# three_digit_CC_PNP.net
KiCad netlist of a schematic drawn in EAGLE
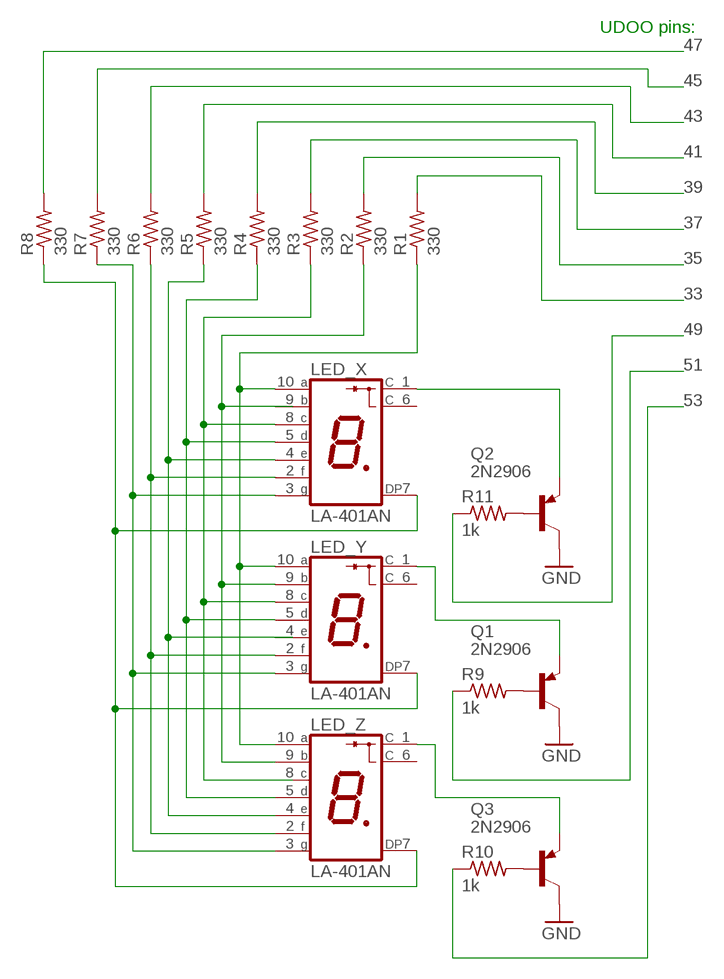
[diagram p0: schematic, sheet 1]

(export (version "E")
  (design (tool "Eeschema 10.0.6"))
  (components
    (comp (ref "LED_X")
      (value "LA-401AN")
      (footprint "eagle-import:LA-401")
      (libsource (lib "eagle-import") (part "LA-401NA"))
    )
    (comp (ref "LED_Y")
      (value "LA-401AN")
      (footprint "eagle-import:LA-401")
      (libsource (lib "eagle-import") (part "LA-401NA"))
    )
    (comp (ref "LED_Z")
      (value "LA-401AN")
      (footprint "eagle-import:LA-401")
      (libsource (lib "eagle-import") (part "LA-401NA"))
    )
    (comp (ref "Q1")
      (value "2N2906")
      (footprint "eagle-import:TO18")
      (libsource (lib "eagle-import") (part "2N2906"))
    )
    (comp (ref "Q2")
      (value "2N2906")
      (footprint "eagle-import:TO18")
      (libsource (lib "eagle-import") (part "2N2906"))
    )
    (comp (ref "Q3")
      (value "2N2906")
      (footprint "eagle-import:TO18")
      (libsource (lib "eagle-import") (part "2N2906"))
    )
    (comp (ref "R1")
      (value "330")
      (footprint "eagle-import:0204_7")
      (libsource (lib "eagle-import") (part "R-US_0204/7"))
    )
    (comp (ref "R2")
      (value "330")
      (footprint "eagle-import:0204_7")
      (libsource (lib "eagle-import") (part "R-US_0204/7"))
    )
    (comp (ref "R3")
      (value "330")
      (footprint "eagle-import:0204_7")
      (libsource (lib "eagle-import") (part "R-US_0204/7"))
    )
    (comp (ref "R4")
      (value "330")
      (footprint "eagle-import:0204_7")
      (libsource (lib "eagle-import") (part "R-US_0204/7"))
    )
    (comp (ref "R5")
      (value "330")
      (footprint "eagle-import:0204_7")
      (libsource (lib "eagle-import") (part "R-US_0204/7"))
    )
    (comp (ref "R6")
      (value "330")
      (footprint "eagle-import:0204_7")
      (libsource (lib "eagle-import") (part "R-US_0204/7"))
    )
    (comp (ref "R7")
      (value "330")
      (footprint "eagle-import:0204_7")
      (libsource (lib "eagle-import") (part "R-US_0204/7"))
    )
    (comp (ref "R8")
      (value "330")
      (footprint "eagle-import:0204_7")
      (libsource (lib "eagle-import") (part "R-US_0204/7"))
    )
    (comp (ref "R9")
      (value "1k")
      (footprint "eagle-import:0204_7")
      (libsource (lib "eagle-import") (part "R-US_0204/7"))
    )
    (comp (ref "R10")
      (value "1k")
      (footprint "eagle-import:0204_7")
      (libsource (lib "eagle-import") (part "R-US_0204/7"))
    )
    (comp (ref "R11")
      (value "1k")
      (footprint "eagle-import:0204_7")
      (libsource (lib "eagle-import") (part "R-US_0204/7"))
    )
  )
  (nets
    (net (code "1") (name "/33") (class "Default")
      (node (ref "R1") (pin "2") (pinfunction "2_2") (pintype "passive"))
    )
    (net (code "2") (name "/35") (class "Default")
      (node (ref "R2") (pin "2") (pinfunction "2_2") (pintype "passive"))
    )
    (net (code "3") (name "/37") (class "Default")
      (node (ref "R3") (pin "2") (pinfunction "2_2") (pintype "passive"))
    )
    (net (code "4") (name "/39") (class "Default")
      (node (ref "R4") (pin "2") (pinfunction "2_2") (pintype "passive"))
    )
    (net (code "5") (name "/41") (class "Default")
      (node (ref "R5") (pin "2") (pinfunction "2_2") (pintype "passive"))
    )
    (net (code "6") (name "/43") (class "Default")
      (node (ref "R6") (pin "2") (pinfunction "2_2") (pintype "passive"))
    )
    (net (code "7") (name "/45") (class "Default")
      (node (ref "R7") (pin "2") (pinfunction "2_2") (pintype "passive"))
    )
    (net (code "8") (name "/47") (class "Default")
      (node (ref "R8") (pin "2") (pinfunction "2_2") (pintype "passive"))
    )
    (net (code "9") (name "/49") (class "Default")
      (node (ref "R11") (pin "1") (pinfunction "1_1") (pintype "passive"))
    )
    (net (code "10") (name "/51") (class "Default")
      (node (ref "R9") (pin "1") (pinfunction "1_1") (pintype "passive"))
    )
    (net (code "11") (name "/53") (class "Default")
      (node (ref "R10") (pin "1") (pinfunction "1_1") (pintype "passive"))
    )
    (net (code "12") (name "GND") (class "Default")
      (node (ref "Q1") (pin "3") (pinfunction "C_3") (pintype "passive"))
      (node (ref "Q2") (pin "3") (pinfunction "C_3") (pintype "passive"))
      (node (ref "Q3") (pin "3") (pinfunction "C_3") (pintype "passive"))
    )
    (net (code "13") (name "Net-(LED_X-A)") (class "Default")
      (node (ref "LED_X") (pin "10") (pinfunction "A_10") (pintype "passive"))
      (node (ref "LED_Y") (pin "10") (pinfunction "A_10") (pintype "passive"))
      (node (ref "LED_Z") (pin "10") (pinfunction "A_10") (pintype "passive"))
      (node (ref "R1") (pin "1") (pinfunction "1_1") (pintype "passive"))
    )
    (net (code "14") (name "Net-(LED_X-C-Pad8)") (class "Default")
      (node (ref "LED_X") (pin "8") (pinfunction "C_8") (pintype "passive"))
      (node (ref "LED_Y") (pin "8") (pinfunction "C_8") (pintype "passive"))
      (node (ref "R3") (pin "1") (pinfunction "1_1") (pintype "passive"))
    )
    (net (code "15") (name "Net-(LED_X-D)") (class "Default")
      (node (ref "LED_X") (pin "5") (pinfunction "D_5") (pintype "passive"))
      (node (ref "LED_Y") (pin "5") (pinfunction "D_5") (pintype "passive"))
      (node (ref "LED_Z") (pin "5") (pinfunction "D_5") (pintype "passive"))
      (node (ref "R4") (pin "1") (pinfunction "1_1") (pintype "passive"))
    )
    (net (code "16") (name "Net-(LED_X-DP)") (class "Default")
      (node (ref "LED_X") (pin "7") (pinfunction "DP_7") (pintype "passive"))
      (node (ref "LED_Y") (pin "7") (pinfunction "DP_7") (pintype "passive"))
      (node (ref "LED_Z") (pin "7") (pinfunction "DP_7") (pintype "passive"))
      (node (ref "R8") (pin "1") (pinfunction "1_1") (pintype "passive"))
    )
    (net (code "17") (name "Net-(LED_X-E)") (class "Default")
      (node (ref "LED_X") (pin "4") (pinfunction "E_4") (pintype "passive"))
      (node (ref "LED_Z") (pin "4") (pinfunction "E_4") (pintype "passive"))
      (node (ref "R5") (pin "1") (pinfunction "1_1") (pintype "passive"))
    )
    (net (code "18") (name "Net-(LED_X-F)") (class "Default")
      (node (ref "LED_X") (pin "2") (pinfunction "F_2") (pintype "passive"))
      (node (ref "LED_Y") (pin "2") (pinfunction "F_2") (pintype "passive"))
      (node (ref "LED_Z") (pin "2") (pinfunction "F_2") (pintype "passive"))
      (node (ref "R6") (pin "1") (pinfunction "1_1") (pintype "passive"))
    )
    (net (code "19") (name "Net-(LED_X-G)") (class "Default")
      (node (ref "LED_X") (pin "3") (pinfunction "G_3") (pintype "passive"))
      (node (ref "LED_Y") (pin "3") (pinfunction "G_3") (pintype "passive"))
      (node (ref "LED_Z") (pin "3") (pinfunction "G_3") (pintype "passive"))
      (node (ref "R7") (pin "1") (pinfunction "1_1") (pintype "passive"))
    )
    (net (code "20") (name "Net-(LED_Y-B)") (class "Default")
      (node (ref "LED_Y") (pin "9") (pinfunction "B_9") (pintype "passive"))
      (node (ref "LED_Z") (pin "9") (pinfunction "B_9") (pintype "passive"))
      (node (ref "R2") (pin "1") (pinfunction "1_1") (pintype "passive"))
    )
    (net (code "21") (name "Net-(Q1-B)") (class "Default")
      (node (ref "Q1") (pin "2") (pinfunction "B_2") (pintype "passive"))
      (node (ref "R9") (pin "2") (pinfunction "2_2") (pintype "passive"))
    )
    (net (code "22") (name "Net-(Q1-E)") (class "Default")
      (node (ref "LED_Y") (pin "1") (pinfunction "C_1") (pintype "passive"))
      (node (ref "Q1") (pin "1") (pinfunction "E_1") (pintype "passive"))
    )
    (net (code "23") (name "Net-(Q2-B)") (class "Default")
      (node (ref "Q2") (pin "2") (pinfunction "B_2") (pintype "passive"))
      (node (ref "R11") (pin "2") (pinfunction "2_2") (pintype "passive"))
    )
    (net (code "24") (name "Net-(Q2-E)") (class "Default")
      (node (ref "LED_X") (pin "1") (pinfunction "C_1") (pintype "passive"))
      (node (ref "Q2") (pin "1") (pinfunction "E_1") (pintype "passive"))
    )
    (net (code "25") (name "Net-(Q3-B)") (class "Default")
      (node (ref "Q3") (pin "2") (pinfunction "B_2") (pintype "passive"))
      (node (ref "R10") (pin "2") (pinfunction "2_2") (pintype "passive"))
    )
    (net (code "26") (name "Net-(Q3-E)") (class "Default")
      (node (ref "LED_Z") (pin "1") (pinfunction "C_1") (pintype "passive"))
      (node (ref "Q3") (pin "1") (pinfunction "E_1") (pintype "passive"))
    )
    (net (code "27") (name "unconnected-(LED_X-B-Pad9)") (class "Default")
      (node (ref "LED_X") (pin "9") (pinfunction "B_9") (pintype "passive"))
    )
    (net (code "28") (name "unconnected-(LED_X-C-Pad6)") (class "Default")
      (node (ref "LED_X") (pin "6") (pinfunction "C_6") (pintype "passive"))
    )
    (net (code "29") (name "unconnected-(LED_Y-C-Pad6)") (class "Default")
      (node (ref "LED_Y") (pin "6") (pinfunction "C_6") (pintype "passive"))
    )
    (net (code "30") (name "unconnected-(LED_Y-E-Pad4)") (class "Default")
      (node (ref "LED_Y") (pin "4") (pinfunction "E_4") (pintype "passive"))
    )
    (net (code "31") (name "unconnected-(LED_Z-C-Pad6)") (class "Default")
      (node (ref "LED_Z") (pin "6") (pinfunction "C_6") (pintype "passive"))
    )
    (net (code "32") (name "unconnected-(LED_Z-C-Pad8)") (class "Default")
      (node (ref "LED_Z") (pin "8") (pinfunction "C_8") (pintype "passive"))
    )
  )
)
